# Sheet_2.net
KiCad netlist of a schematic drawn in Altium Designer
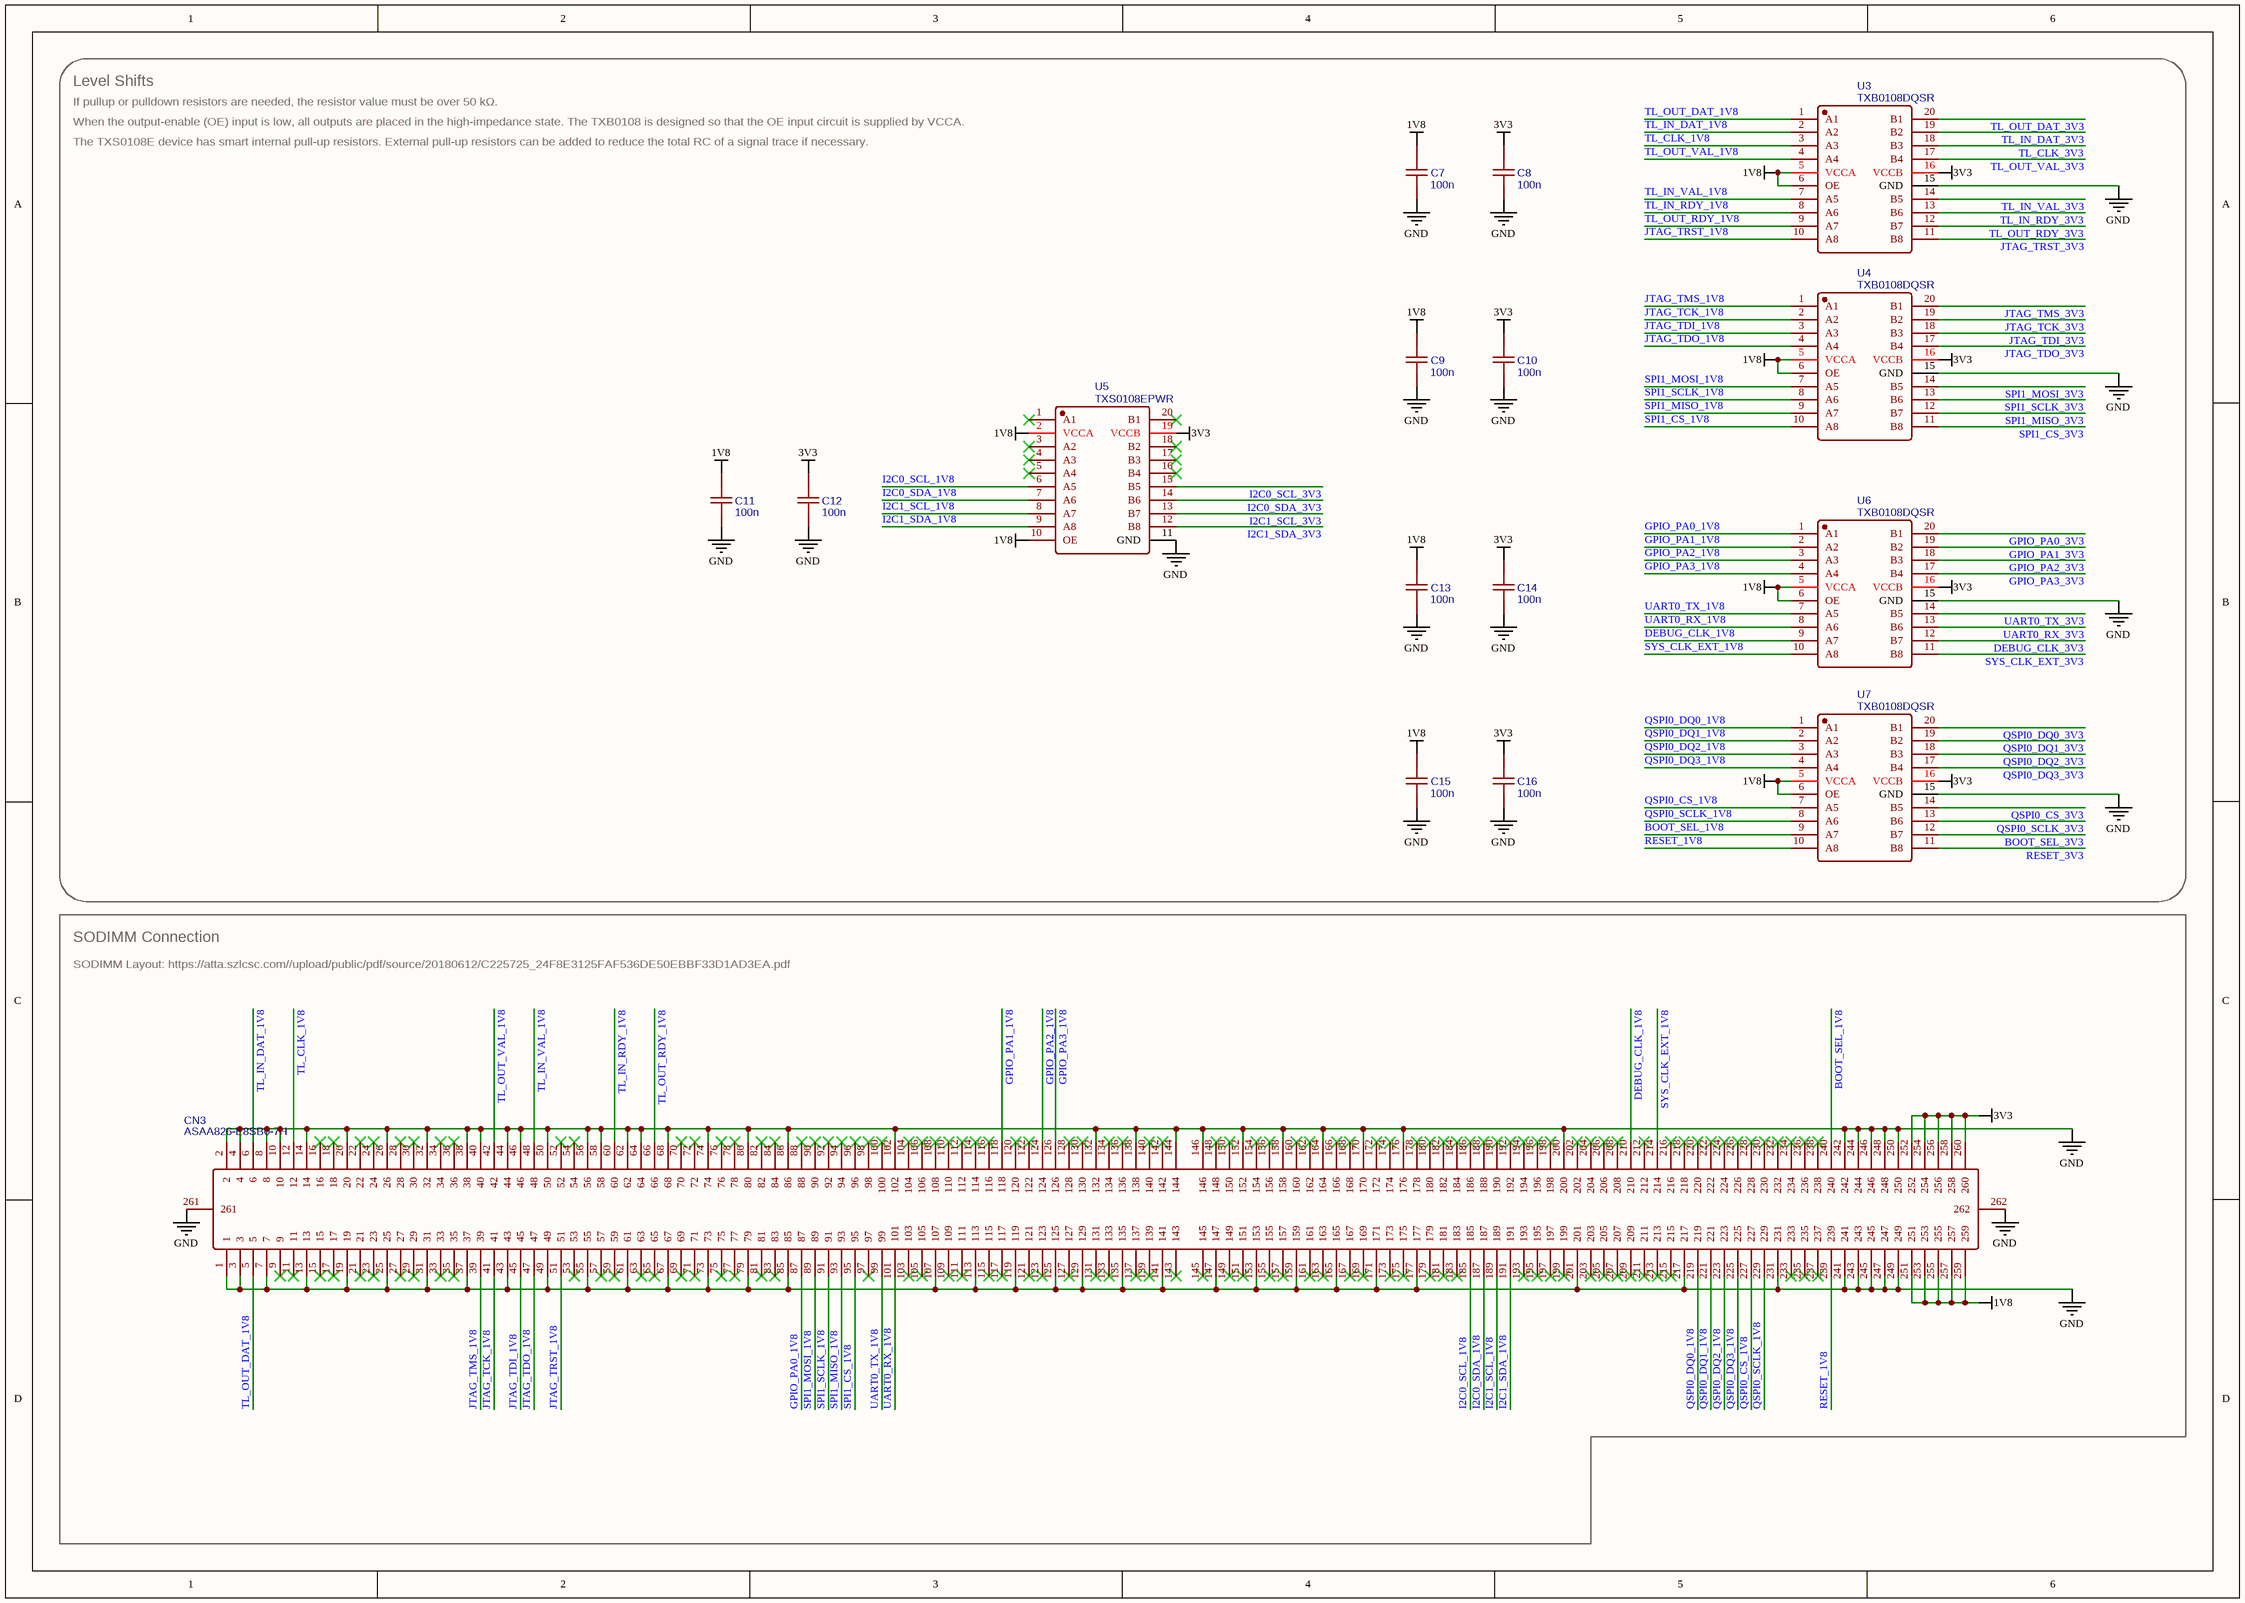
[diagram p0: Sheet_2.schdoc]

(export (version "E")
  (design (tool "Eeschema 10.0.6"))
  (components
    (comp (ref "C7")
      (value "100n")
      (footprint "CAPA-0402")
      (fields
        (field (name "BOM_SUPPLIER PART") "C307331")
        (field (name "BOM_MANUFACTURER PART") "CL05B104KB54PNC")
      )
      (libsource (lib "altium-import") (part "root_1_100n_"))
    )
    (comp (ref "C8")
      (value "100n")
      (footprint "CAPA-0402")
      (fields
        (field (name "BOM_SUPPLIER PART") "C307331")
        (field (name "BOM_MANUFACTURER PART") "CL05B104KB54PNC")
      )
      (libsource (lib "altium-import") (part "root_1_100n_"))
    )
    (comp (ref "C9")
      (value "100n")
      (footprint "CAPA-0402")
      (fields
        (field (name "BOM_SUPPLIER PART") "C307331")
        (field (name "BOM_MANUFACTURER PART") "CL05B104KB54PNC")
      )
      (libsource (lib "altium-import") (part "root_1_100n_"))
    )
    (comp (ref "C10")
      (value "100n")
      (footprint "CAPA-0402")
      (fields
        (field (name "BOM_SUPPLIER PART") "C307331")
        (field (name "BOM_MANUFACTURER PART") "CL05B104KB54PNC")
      )
      (libsource (lib "altium-import") (part "root_1_100n_"))
    )
    (comp (ref "C11")
      (value "100n")
      (footprint "CAPA-0402")
      (fields
        (field (name "BOM_SUPPLIER PART") "C307331")
        (field (name "BOM_MANUFACTURER PART") "CL05B104KB54PNC")
      )
      (libsource (lib "altium-import") (part "root_1_100n_"))
    )
    (comp (ref "C12")
      (value "100n")
      (footprint "CAPA-0402")
      (fields
        (field (name "BOM_SUPPLIER PART") "C307331")
        (field (name "BOM_MANUFACTURER PART") "CL05B104KB54PNC")
      )
      (libsource (lib "altium-import") (part "root_1_100n_"))
    )
    (comp (ref "C13")
      (value "100n")
      (footprint "CAPA-0402")
      (fields
        (field (name "BOM_SUPPLIER PART") "C307331")
        (field (name "BOM_MANUFACTURER PART") "CL05B104KB54PNC")
      )
      (libsource (lib "altium-import") (part "root_1_100n_"))
    )
    (comp (ref "C14")
      (value "100n")
      (footprint "CAPA-0402")
      (fields
        (field (name "BOM_SUPPLIER PART") "C307331")
        (field (name "BOM_MANUFACTURER PART") "CL05B104KB54PNC")
      )
      (libsource (lib "altium-import") (part "root_1_100n_"))
    )
    (comp (ref "C15")
      (value "100n")
      (footprint "CAPA-0402")
      (fields
        (field (name "BOM_SUPPLIER PART") "C307331")
        (field (name "BOM_MANUFACTURER PART") "CL05B104KB54PNC")
      )
      (libsource (lib "altium-import") (part "root_1_100n_"))
    )
    (comp (ref "C16")
      (value "100n")
      (footprint "CAPA-0402")
      (fields
        (field (name "BOM_SUPPLIER PART") "C307331")
        (field (name "BOM_MANUFACTURER PART") "CL05B104KB54PNC")
      )
      (libsource (lib "altium-import") (part "root_1_100n_"))
    )
    (comp (ref "CN3")
      (value "ASAA826-E8SB0-7H")
      (footprint "CONN-SMD_ASAA826-E8SB0-7H")
      (fields (field (name "BOM_SUPPLIER PART") "C2761395"))
      (libsource (lib "altium-import") (part "root_0_ASAA826-E8SB0-7H_"))
    )
    (comp (ref "U3")
      (value "TXB0108DQSR")
      (footprint "SON-20_L4.0-W2.0-P0.40-BL")
      (fields (field (name "BOM_SUPPLIER PART") "C427057"))
      (libsource (lib "altium-import") (part "root_0_TXB0108DQSR_"))
    )
    (comp (ref "U4")
      (value "TXB0108DQSR")
      (footprint "SON-20_L4.0-W2.0-P0.40-BL")
      (fields (field (name "BOM_SUPPLIER PART") "C427057"))
      (libsource (lib "altium-import") (part "root_0_TXB0108DQSR_"))
    )
    (comp (ref "U5")
      (value "TXS0108EPWR")
      (footprint "TSSOP-20_L6.5-W4.4-P0.65-LS6.4-BL")
      (fields (field (name "BOM_SUPPLIER PART") "C17206"))
      (libsource (lib "altium-import") (part "root_0_TXS0108EPWR_"))
    )
    (comp (ref "U6")
      (value "TXB0108DQSR")
      (footprint "SON-20_L4.0-W2.0-P0.40-BL")
      (fields (field (name "BOM_SUPPLIER PART") "C427057"))
      (libsource (lib "altium-import") (part "root_0_TXB0108DQSR_"))
    )
    (comp (ref "U7")
      (value "TXB0108DQSR")
      (footprint "SON-20_L4.0-W2.0-P0.40-BL")
      (fields (field (name "BOM_SUPPLIER PART") "C427057"))
      (libsource (lib "altium-import") (part "root_0_TXB0108DQSR_"))
    )
  )
  (nets
    (net (code "1") (name "/BOOT_SEL_1V8") (class "Default")
      (node (ref "CN3") (pin "240") (pinfunction "240_240") (pintype "passive"))
      (node (ref "U7") (pin "9") (pinfunction "A7_9") (pintype "passive"))
    )
    (net (code "2") (name "/BOOT_SEL_3V3") (class "Default")
      (node (ref "U7") (pin "12") (pinfunction "B7_12") (pintype "passive"))
    )
    (net (code "3") (name "/DEBUG_CLK_1V8") (class "Default")
      (node (ref "CN3") (pin "210") (pinfunction "210_210") (pintype "passive"))
      (node (ref "U6") (pin "9") (pinfunction "A7_9") (pintype "passive"))
    )
    (net (code "4") (name "/DEBUG_CLK_3V3") (class "Default")
      (node (ref "U6") (pin "12") (pinfunction "B7_12") (pintype "passive"))
    )
    (net (code "5") (name "/GPIO_PA0_1V8") (class "Default")
      (node (ref "CN3") (pin "87") (pinfunction "87_87") (pintype "passive"))
      (node (ref "U6") (pin "1") (pinfunction "A1_1") (pintype "passive"))
    )
    (net (code "6") (name "/GPIO_PA0_3V3") (class "Default")
      (node (ref "U6") (pin "20") (pinfunction "B1_20") (pintype "passive"))
    )
    (net (code "7") (name "/GPIO_PA1_1V8") (class "Default")
      (node (ref "CN3") (pin "118") (pinfunction "118_118") (pintype "passive"))
      (node (ref "U6") (pin "2") (pinfunction "A2_2") (pintype "passive"))
    )
    (net (code "8") (name "/GPIO_PA1_3V3") (class "Default")
      (node (ref "U6") (pin "19") (pinfunction "B2_19") (pintype "passive"))
    )
    (net (code "9") (name "/GPIO_PA2_1V8") (class "Default")
      (node (ref "CN3") (pin "124") (pinfunction "124_124") (pintype "passive"))
      (node (ref "U6") (pin "3") (pinfunction "A3_3") (pintype "passive"))
    )
    (net (code "10") (name "/GPIO_PA2_3V3") (class "Default")
      (node (ref "U6") (pin "18") (pinfunction "B3_18") (pintype "passive"))
    )
    (net (code "11") (name "/GPIO_PA3_1V8") (class "Default")
      (node (ref "CN3") (pin "126") (pinfunction "126_126") (pintype "passive"))
      (node (ref "U6") (pin "4") (pinfunction "A4_4") (pintype "passive"))
    )
    (net (code "12") (name "/GPIO_PA3_3V3") (class "Default")
      (node (ref "U6") (pin "17") (pinfunction "B4_17") (pintype "passive"))
    )
    (net (code "13") (name "/I2C0_SCL_1V8") (class "Default")
      (node (ref "CN3") (pin "185") (pinfunction "185_185") (pintype "passive"))
      (node (ref "U5") (pin "6") (pinfunction "A5_6") (pintype "passive"))
    )
    (net (code "14") (name "/I2C0_SCL_3V3") (class "Default")
      (node (ref "U5") (pin "15") (pinfunction "B5_15") (pintype "passive"))
    )
    (net (code "15") (name "/I2C0_SDA_1V8") (class "Default")
      (node (ref "CN3") (pin "187") (pinfunction "187_187") (pintype "passive"))
      (node (ref "U5") (pin "7") (pinfunction "A6_7") (pintype "passive"))
    )
    (net (code "16") (name "/I2C0_SDA_3V3") (class "Default")
      (node (ref "U5") (pin "14") (pinfunction "B6_14") (pintype "passive"))
    )
    (net (code "17") (name "/I2C1_SCL_1V8") (class "Default")
      (node (ref "CN3") (pin "189") (pinfunction "189_189") (pintype "passive"))
      (node (ref "U5") (pin "8") (pinfunction "A7_8") (pintype "passive"))
    )
    (net (code "18") (name "/I2C1_SCL_3V3") (class "Default")
      (node (ref "U5") (pin "13") (pinfunction "B7_13") (pintype "passive"))
    )
    (net (code "19") (name "/I2C1_SDA_1V8") (class "Default")
      (node (ref "CN3") (pin "191") (pinfunction "191_191") (pintype "passive"))
      (node (ref "U5") (pin "9") (pinfunction "A8_9") (pintype "passive"))
    )
    (net (code "20") (name "/I2C1_SDA_3V3") (class "Default")
      (node (ref "U5") (pin "12") (pinfunction "B8_12") (pintype "passive"))
    )
    (net (code "21") (name "/JTAG_TCK_1V8") (class "Default")
      (node (ref "CN3") (pin "41") (pinfunction "41_41") (pintype "passive"))
      (node (ref "U4") (pin "2") (pinfunction "A2_2") (pintype "passive"))
    )
    (net (code "22") (name "/JTAG_TCK_3V3") (class "Default")
      (node (ref "U4") (pin "19") (pinfunction "B2_19") (pintype "passive"))
    )
    (net (code "23") (name "/JTAG_TDI_1V8") (class "Default")
      (node (ref "CN3") (pin "45") (pinfunction "45_45") (pintype "passive"))
      (node (ref "U4") (pin "3") (pinfunction "A3_3") (pintype "passive"))
    )
    (net (code "24") (name "/JTAG_TDI_3V3") (class "Default")
      (node (ref "U4") (pin "18") (pinfunction "B3_18") (pintype "passive"))
    )
    (net (code "25") (name "/JTAG_TDO_1V8") (class "Default")
      (node (ref "CN3") (pin "47") (pinfunction "47_47") (pintype "passive"))
      (node (ref "U4") (pin "4") (pinfunction "A4_4") (pintype "passive"))
    )
    (net (code "26") (name "/JTAG_TDO_3V3") (class "Default")
      (node (ref "U4") (pin "17") (pinfunction "B4_17") (pintype "passive"))
    )
    (net (code "27") (name "/JTAG_TMS_1V8") (class "Default")
      (node (ref "CN3") (pin "39") (pinfunction "39_39") (pintype "passive"))
      (node (ref "U4") (pin "1") (pinfunction "A1_1") (pintype "passive"))
    )
    (net (code "28") (name "/JTAG_TMS_3V3") (class "Default")
      (node (ref "U4") (pin "20") (pinfunction "B1_20") (pintype "passive"))
    )
    (net (code "29") (name "/JTAG_TRST_1V8") (class "Default")
      (node (ref "CN3") (pin "51") (pinfunction "51_51") (pintype "passive"))
      (node (ref "U3") (pin "10") (pinfunction "A8_10") (pintype "passive"))
    )
    (net (code "30") (name "/JTAG_TRST_3V3") (class "Default")
      (node (ref "U3") (pin "11") (pinfunction "B8_11") (pintype "passive"))
    )
    (net (code "31") (name "/QSPI0_CS_1V8") (class "Default")
      (node (ref "CN3") (pin "227") (pinfunction "227_227") (pintype "passive"))
      (node (ref "U7") (pin "7") (pinfunction "A5_7") (pintype "passive"))
    )
    (net (code "32") (name "/QSPI0_CS_3V3") (class "Default")
      (node (ref "U7") (pin "14") (pinfunction "B5_14") (pintype "passive"))
    )
    (net (code "33") (name "/QSPI0_DQ0_1V8") (class "Default")
      (node (ref "CN3") (pin "219") (pinfunction "219_219") (pintype "passive"))
      (node (ref "U7") (pin "1") (pinfunction "A1_1") (pintype "passive"))
    )
    (net (code "34") (name "/QSPI0_DQ0_3V3") (class "Default")
      (node (ref "U7") (pin "20") (pinfunction "B1_20") (pintype "passive"))
    )
    (net (code "35") (name "/QSPI0_DQ1_1V8") (class "Default")
      (node (ref "CN3") (pin "221") (pinfunction "221_221") (pintype "passive"))
      (node (ref "U7") (pin "2") (pinfunction "A2_2") (pintype "passive"))
    )
    (net (code "36") (name "/QSPI0_DQ1_3V3") (class "Default")
      (node (ref "U7") (pin "19") (pinfunction "B2_19") (pintype "passive"))
    )
    (net (code "37") (name "/QSPI0_DQ2_1V8") (class "Default")
      (node (ref "CN3") (pin "223") (pinfunction "223_223") (pintype "passive"))
      (node (ref "U7") (pin "3") (pinfunction "A3_3") (pintype "passive"))
    )
    (net (code "38") (name "/QSPI0_DQ2_3V3") (class "Default")
      (node (ref "U7") (pin "18") (pinfunction "B3_18") (pintype "passive"))
    )
    (net (code "39") (name "/QSPI0_DQ3_1V8") (class "Default")
      (node (ref "CN3") (pin "225") (pinfunction "225_225") (pintype "passive"))
      (node (ref "U7") (pin "4") (pinfunction "A4_4") (pintype "passive"))
    )
    (net (code "40") (name "/QSPI0_DQ3_3V3") (class "Default")
      (node (ref "U7") (pin "17") (pinfunction "B4_17") (pintype "passive"))
    )
    (net (code "41") (name "/QSPI0_SCLK_1V8") (class "Default")
      (node (ref "CN3") (pin "229") (pinfunction "229_229") (pintype "passive"))
      (node (ref "U7") (pin "8") (pinfunction "A6_8") (pintype "passive"))
    )
    (net (code "42") (name "/QSPI0_SCLK_3V3") (class "Default")
      (node (ref "U7") (pin "13") (pinfunction "B6_13") (pintype "passive"))
    )
    (net (code "43") (name "/RESET_1V8") (class "Default")
      (node (ref "CN3") (pin "239") (pinfunction "239_239") (pintype "passive"))
      (node (ref "U7") (pin "10") (pinfunction "A8_10") (pintype "passive"))
    )
    (net (code "44") (name "/RESET_3V3") (class "Default")
      (node (ref "U7") (pin "11") (pinfunction "B8_11") (pintype "passive"))
    )
    (net (code "45") (name "/SPI1_CS_1V8") (class "Default")
      (node (ref "CN3") (pin "95") (pinfunction "95_95") (pintype "passive"))
      (node (ref "U4") (pin "10") (pinfunction "A8_10") (pintype "passive"))
    )
    (net (code "46") (name "/SPI1_CS_3V3") (class "Default")
      (node (ref "U4") (pin "11") (pinfunction "B8_11") (pintype "passive"))
    )
    (net (code "47") (name "/SPI1_MISO_1V8") (class "Default")
      (node (ref "CN3") (pin "93") (pinfunction "93_93") (pintype "passive"))
      (node (ref "U4") (pin "9") (pinfunction "A7_9") (pintype "passive"))
    )
    (net (code "48") (name "/SPI1_MISO_3V3") (class "Default")
      (node (ref "U4") (pin "12") (pinfunction "B7_12") (pintype "passive"))
    )
    (net (code "49") (name "/SPI1_MOSI_1V8") (class "Default")
      (node (ref "CN3") (pin "89") (pinfunction "89_89") (pintype "passive"))
      (node (ref "U4") (pin "7") (pinfunction "A5_7") (pintype "passive"))
    )
    (net (code "50") (name "/SPI1_MOSI_3V3") (class "Default")
      (node (ref "U4") (pin "14") (pinfunction "B5_14") (pintype "passive"))
    )
    (net (code "51") (name "/SPI1_SCLK_1V8") (class "Default")
      (node (ref "CN3") (pin "91") (pinfunction "91_91") (pintype "passive"))
      (node (ref "U4") (pin "8") (pinfunction "A6_8") (pintype "passive"))
    )
    (net (code "52") (name "/SPI1_SCLK_3V3") (class "Default")
      (node (ref "U4") (pin "13") (pinfunction "B6_13") (pintype "passive"))
    )
    (net (code "53") (name "/SYS_CLK_EXT_1V8") (class "Default")
      (node (ref "CN3") (pin "214") (pinfunction "214_214") (pintype "passive"))
      (node (ref "U6") (pin "10") (pinfunction "A8_10") (pintype "passive"))
    )
    (net (code "54") (name "/SYS_CLK_EXT_3V3") (class "Default")
      (node (ref "U6") (pin "11") (pinfunction "B8_11") (pintype "passive"))
    )
    (net (code "55") (name "/TL_CLK_1V8") (class "Default")
      (node (ref "CN3") (pin "12") (pinfunction "12_12") (pintype "passive"))
      (node (ref "U3") (pin "3") (pinfunction "A3_3") (pintype "passive"))
    )
    (net (code "56") (name "/TL_CLK_3V3") (class "Default")
      (node (ref "U3") (pin "18") (pinfunction "B3_18") (pintype "passive"))
    )
    (net (code "57") (name "/TL_IN_DAT_1V8") (class "Default")
      (node (ref "CN3") (pin "6") (pinfunction "6_6") (pintype "passive"))
      (node (ref "U3") (pin "2") (pinfunction "A2_2") (pintype "passive"))
    )
    (net (code "58") (name "/TL_IN_DAT_3V3") (class "Default")
      (node (ref "U3") (pin "19") (pinfunction "B2_19") (pintype "passive"))
    )
    (net (code "59") (name "/TL_IN_RDY_1V8") (class "Default")
      (node (ref "CN3") (pin "60") (pinfunction "60_60") (pintype "passive"))
      (node (ref "U3") (pin "8") (pinfunction "A6_8") (pintype "passive"))
    )
    (net (code "60") (name "/TL_IN_RDY_3V3") (class "Default")
      (node (ref "U3") (pin "13") (pinfunction "B6_13") (pintype "passive"))
    )
    (net (code "61") (name "/TL_IN_VAL_1V8") (class "Default")
      (node (ref "CN3") (pin "48") (pinfunction "48_48") (pintype "passive"))
      (node (ref "U3") (pin "7") (pinfunction "A5_7") (pintype "passive"))
    )
    (net (code "62") (name "/TL_IN_VAL_3V3") (class "Default")
      (node (ref "U3") (pin "14") (pinfunction "B5_14") (pintype "passive"))
    )
    (net (code "63") (name "/TL_OUT_DAT_1V8") (class "Default")
      (node (ref "CN3") (pin "5") (pinfunction "5_5") (pintype "passive"))
      (node (ref "U3") (pin "1") (pinfunction "A1_1") (pintype "passive"))
    )
    (net (code "64") (name "/TL_OUT_DAT_3V3") (class "Default")
      (node (ref "U3") (pin "20") (pinfunction "B1_20") (pintype "passive"))
    )
    (net (code "65") (name "/TL_OUT_RDY_1V8") (class "Default")
      (node (ref "CN3") (pin "66") (pinfunction "66_66") (pintype "passive"))
      (node (ref "U3") (pin "9") (pinfunction "A7_9") (pintype "passive"))
    )
    (net (code "66") (name "/TL_OUT_RDY_3V3") (class "Default")
      (node (ref "U3") (pin "12") (pinfunction "B7_12") (pintype "passive"))
    )
    (net (code "67") (name "/TL_OUT_VAL_1V8") (class "Default")
      (node (ref "CN3") (pin "42") (pinfunction "42_42") (pintype "passive"))
      (node (ref "U3") (pin "4") (pinfunction "A4_4") (pintype "passive"))
    )
    (net (code "68") (name "/TL_OUT_VAL_3V3") (class "Default")
      (node (ref "U3") (pin "17") (pinfunction "B4_17") (pintype "passive"))
    )
    (net (code "69") (name "/UART0_RX_1V8") (class "Default")
      (node (ref "CN3") (pin "101") (pinfunction "101_101") (pintype "passive"))
      (node (ref "U6") (pin "8") (pinfunction "A6_8") (pintype "passive"))
    )
    (net (code "70") (name "/UART0_RX_3V3") (class "Default")
      (node (ref "U6") (pin "13") (pinfunction "B6_13") (pintype "passive"))
    )
    (net (code "71") (name "/UART0_TX_1V8") (class "Default")
      (node (ref "CN3") (pin "99") (pinfunction "99_99") (pintype "passive"))
      (node (ref "U6") (pin "7") (pinfunction "A5_7") (pintype "passive"))
    )
    (net (code "72") (name "/UART0_TX_3V3") (class "Default")
      (node (ref "U6") (pin "14") (pinfunction "B5_14") (pintype "passive"))
    )
    (net (code "73") (name "1V8") (class "Default")
      (node (ref "C11") (pin "2") (pinfunction "2_2") (pintype "passive"))
      (node (ref "C13") (pin "2") (pinfunction "2_2") (pintype "passive"))
      (node (ref "C15") (pin "2") (pinfunction "2_2") (pintype "passive"))
      (node (ref "C7") (pin "2") (pinfunction "2_2") (pintype "passive"))
      (node (ref "C9") (pin "2") (pinfunction "2_2") (pintype "passive"))
      (node (ref "CN3") (pin "251") (pinfunction "251_251") (pintype "passive"))
      (node (ref "CN3") (pin "253") (pinfunction "253_253") (pintype "passive"))
      (node (ref "CN3") (pin "255") (pinfunction "255_255") (pintype "passive"))
      (node (ref "CN3") (pin "257") (pinfunction "257_257") (pintype "passive"))
      (node (ref "CN3") (pin "259") (pinfunction "259_259") (pintype "passive"))
      (node (ref "U3") (pin "5") (pinfunction "VCCA_5") (pintype "passive"))
      (node (ref "U3") (pin "6") (pinfunction "OE_6") (pintype "passive"))
      (node (ref "U4") (pin "5") (pinfunction "VCCA_5") (pintype "passive"))
      (node (ref "U4") (pin "6") (pinfunction "OE_6") (pintype "passive"))
      (node (ref "U5") (pin "10") (pinfunction "OE_10") (pintype "passive"))
      (node (ref "U5") (pin "2") (pinfunction "VCCA_2") (pintype "passive"))
      (node (ref "U6") (pin "5") (pinfunction "VCCA_5") (pintype "passive"))
      (node (ref "U6") (pin "6") (pinfunction "OE_6") (pintype "passive"))
      (node (ref "U7") (pin "5") (pinfunction "VCCA_5") (pintype "passive"))
      (node (ref "U7") (pin "6") (pinfunction "OE_6") (pintype "passive"))
    )
    (net (code "74") (name "3V3") (class "Default")
      (node (ref "C10") (pin "2") (pinfunction "2_2") (pintype "passive"))
      (node (ref "C12") (pin "2") (pinfunction "2_2") (pintype "passive"))
      (node (ref "C14") (pin "2") (pinfunction "2_2") (pintype "passive"))
      (node (ref "C16") (pin "2") (pinfunction "2_2") (pintype "passive"))
      (node (ref "C8") (pin "2") (pinfunction "2_2") (pintype "passive"))
      (node (ref "CN3") (pin "252") (pinfunction "252_252") (pintype "passive"))
      (node (ref "CN3") (pin "254") (pinfunction "254_254") (pintype "passive"))
      (node (ref "CN3") (pin "256") (pinfunction "256_256") (pintype "passive"))
      (node (ref "CN3") (pin "258") (pinfunction "258_258") (pintype "passive"))
      (node (ref "CN3") (pin "260") (pinfunction "260_260") (pintype "passive"))
      (node (ref "U3") (pin "16") (pinfunction "VCCB_16") (pintype "passive"))
      (node (ref "U4") (pin "16") (pinfunction "VCCB_16") (pintype "passive"))
      (node (ref "U5") (pin "19") (pinfunction "VCCB_19") (pintype "passive"))
      (node (ref "U6") (pin "16") (pinfunction "VCCB_16") (pintype "passive"))
      (node (ref "U7") (pin "16") (pinfunction "VCCB_16") (pintype "passive"))
    )
    (net (code "75") (name "GND") (class "Default")
      (node (ref "C10") (pin "1") (pinfunction "1_1") (pintype "passive"))
      (node (ref "C11") (pin "1") (pinfunction "1_1") (pintype "passive"))
      (node (ref "C12") (pin "1") (pinfunction "1_1") (pintype "passive"))
      (node (ref "C13") (pin "1") (pinfunction "1_1") (pintype "passive"))
      (node (ref "C14") (pin "1") (pinfunction "1_1") (pintype "passive"))
      (node (ref "C15") (pin "1") (pinfunction "1_1") (pintype "passive"))
      (node (ref "C16") (pin "1") (pinfunction "1_1") (pintype "passive"))
      (node (ref "C7") (pin "1") (pinfunction "1_1") (pintype "passive"))
      (node (ref "C8") (pin "1") (pinfunction "1_1") (pintype "passive"))
      (node (ref "C9") (pin "1") (pinfunction "1_1") (pintype "passive"))
      (node (ref "CN3") (pin "1") (pinfunction "1_1") (pintype "passive"))
      (node (ref "CN3") (pin "10") (pinfunction "10_10") (pintype "passive"))
      (node (ref "CN3") (pin "102") (pinfunction "102_102") (pintype "passive"))
      (node (ref "CN3") (pin "107") (pinfunction "107_107") (pintype "passive"))
      (node (ref "CN3") (pin "113") (pinfunction "113_113") (pintype "passive"))
      (node (ref "CN3") (pin "119") (pinfunction "119_119") (pintype "passive"))
      (node (ref "CN3") (pin "125") (pinfunction "125_125") (pintype "passive"))
      (node (ref "CN3") (pin "129") (pinfunction "129_129") (pintype "passive"))
      (node (ref "CN3") (pin "13") (pinfunction "13_13") (pintype "passive"))
      (node (ref "CN3") (pin "132") (pinfunction "132_132") (pintype "passive"))
      (node (ref "CN3") (pin "135") (pinfunction "135_135") (pintype "passive"))
      (node (ref "CN3") (pin "138") (pinfunction "138_138") (pintype "passive"))
      (node (ref "CN3") (pin "14") (pinfunction "14_14") (pintype "passive"))
      (node (ref "CN3") (pin "141") (pinfunction "141_141") (pintype "passive"))
      (node (ref "CN3") (pin "144") (pinfunction "144_144") (pintype "passive"))
      (node (ref "CN3") (pin "146") (pinfunction "146_146") (pintype "passive"))
      (node (ref "CN3") (pin "147") (pinfunction "147_147") (pintype "passive"))
      (node (ref "CN3") (pin "152") (pinfunction "152_152") (pintype "passive"))
      (node (ref "CN3") (pin "153") (pinfunction "153_153") (pintype "passive"))
      (node (ref "CN3") (pin "158") (pinfunction "158_158") (pintype "passive"))
      (node (ref "CN3") (pin "159") (pinfunction "159_159") (pintype "passive"))
      (node (ref "CN3") (pin "164") (pinfunction "164_164") (pintype "passive"))
      (node (ref "CN3") (pin "165") (pinfunction "165_165") (pintype "passive"))
      (node (ref "CN3") (pin "170") (pinfunction "170_170") (pintype "passive"))
      (node (ref "CN3") (pin "171") (pinfunction "171_171") (pintype "passive"))
      (node (ref "CN3") (pin "176") (pinfunction "176_176") (pintype "passive"))
      (node (ref "CN3") (pin "177") (pinfunction "177_177") (pintype "passive"))
      (node (ref "CN3") (pin "19") (pinfunction "19_19") (pintype "passive"))
      (node (ref "CN3") (pin "2") (pinfunction "2_2") (pintype "passive"))
      (node (ref "CN3") (pin "20") (pinfunction "20_20") (pintype "passive"))
      (node (ref "CN3") (pin "200") (pinfunction "200_200") (pintype "passive"))
      (node (ref "CN3") (pin "201") (pinfunction "201_201") (pintype "passive"))
      (node (ref "CN3") (pin "217") (pinfunction "217_217") (pintype "passive"))
      (node (ref "CN3") (pin "231") (pinfunction "231_231") (pintype "passive"))
      (node (ref "CN3") (pin "241") (pinfunction "241_241") (pintype "passive"))
      (node (ref "CN3") (pin "242") (pinfunction "242_242") (pintype "passive"))
      (node (ref "CN3") (pin "243") (pinfunction "243_243") (pintype "passive"))
      (node (ref "CN3") (pin "244") (pinfunction "244_244") (pintype "passive"))
      (node (ref "CN3") (pin "245") (pinfunction "245_245") (pintype "passive"))
      (node (ref "CN3") (pin "246") (pinfunction "246_246") (pintype "passive"))
      (node (ref "CN3") (pin "247") (pinfunction "247_247") (pintype "passive"))
      (node (ref "CN3") (pin "248") (pinfunction "248_248") (pintype "passive"))
      (node (ref "CN3") (pin "249") (pinfunction "249_249") (pintype "passive"))
      (node (ref "CN3") (pin "25") (pinfunction "25_25") (pintype "passive"))
      (node (ref "CN3") (pin "250") (pinfunction "250_250") (pintype "passive"))
      (node (ref "CN3") (pin "26") (pinfunction "26_26") (pintype "passive"))
      (node (ref "CN3") (pin "261") (pinfunction "261_261") (pintype "passive"))
      (node (ref "CN3") (pin "262") (pinfunction "262_262") (pintype "passive"))
      (node (ref "CN3") (pin "3") (pinfunction "3_3") (pintype "passive"))
      (node (ref "CN3") (pin "31") (pinfunction "31_31") (pintype "passive"))
      (node (ref "CN3") (pin "32") (pinfunction "32_32") (pintype "passive"))
      (node (ref "CN3") (pin "37") (pinfunction "37_37") (pintype "passive"))
      (node (ref "CN3") (pin "38") (pinfunction "38_38") (pintype "passive"))
      (node (ref "CN3") (pin "4") (pinfunction "4_4") (pintype "passive"))
      (node (ref "CN3") (pin "40") (pinfunction "40_40") (pintype "passive"))
      (node (ref "CN3") (pin "43") (pinfunction "43_43") (pintype "passive"))
      (node (ref "CN3") (pin "44") (pinfunction "44_44") (pintype "passive"))
      (node (ref "CN3") (pin "46") (pinfunction "46_46") (pintype "passive"))
      (node (ref "CN3") (pin "49") (pinfunction "49_49") (pintype "passive"))
      (node (ref "CN3") (pin "50") (pinfunction "50_50") (pintype "passive"))
      (node (ref "CN3") (pin "55") (pinfunction "55_55") (pintype "passive"))
      (node (ref "CN3") (pin "56") (pinfunction "56_56") (pintype "passive"))
      (node (ref "CN3") (pin "58") (pinfunction "58_58") (pintype "passive"))
      (node (ref "CN3") (pin "61") (pinfunction "61_61") (pintype "passive"))
      (node (ref "CN3") (pin "62") (pinfunction "62_62") (pintype "passive"))
      (node (ref "CN3") (pin "64") (pinfunction "64_64") (pintype "passive"))
      (node (ref "CN3") (pin "67") (pinfunction "67_67") (pintype "passive"))
      (node (ref "CN3") (pin "68") (pinfunction "68_68") (pintype "passive"))
      (node (ref "CN3") (pin "7") (pinfunction "7_7") (pintype "passive"))
      (node (ref "CN3") (pin "73") (pinfunction "73_73") (pintype "passive"))
      (node (ref "CN3") (pin "74") (pinfunction "74_74") (pintype "passive"))
      (node (ref "CN3") (pin "79") (pinfunction "79_79") (pintype "passive"))
      (node (ref "CN3") (pin "8") (pinfunction "8_8") (pintype "passive"))
      (node (ref "CN3") (pin "80") (pinfunction "80_80") (pintype "passive"))
      (node (ref "CN3") (pin "85") (pinfunction "85_85") (pintype "passive"))
      (node (ref "CN3") (pin "86") (pinfunction "86_86") (pintype "passive"))
      (node (ref "U3") (pin "15") (pinfunction "GND_15") (pintype "passive"))
      (node (ref "U4") (pin "15") (pinfunction "GND_15") (pintype "passive"))
      (node (ref "U5") (pin "11") (pinfunction "GND_11") (pintype "passive"))
      (node (ref "U6") (pin "15") (pinfunction "GND_15") (pintype "passive"))
      (node (ref "U7") (pin "15") (pinfunction "GND_15") (pintype "passive"))
    )
    (net (code "76") (name "unconnected-(CN3-Pad9)") (class "Default")
      (node (ref "CN3") (pin "9") (pinfunction "9_9") (pintype "passive+no_connect"))
    )
    (net (code "77") (name "unconnected-(CN3-Pad11)") (class "Default")
      (node (ref "CN3") (pin "11") (pinfunction "11_11") (pintype "passive+no_connect"))
    )
    (net (code "78") (name "unconnected-(CN3-Pad15)") (class "Default")
      (node (ref "CN3") (pin "15") (pinfunction "15_15") (pintype "passive+no_connect"))
    )
    (net (code "79") (name "unconnected-(CN3-Pad16)") (class "Default")
      (node (ref "CN3") (pin "16") (pinfunction "16_16") (pintype "passive+no_connect"))
    )
    (net (code "80") (name "unconnected-(CN3-Pad17)") (class "Default")
      (node (ref "CN3") (pin "17") (pinfunction "17_17") (pintype "passive+no_connect"))
    )
    (net (code "81") (name "unconnected-(CN3-Pad18)") (class "Default")
      (node (ref "CN3") (pin "18") (pinfunction "18_18") (pintype "passive+no_connect"))
    )
    (net (code "82") (name "unconnected-(CN3-Pad21)") (class "Default")
      (node (ref "CN3") (pin "21") (pinfunction "21_21") (pintype "passive+no_connect"))
    )
    (net (code "83") (name "unconnected-(CN3-Pad22)") (class "Default")
      (node (ref "CN3") (pin "22") (pinfunction "22_22") (pintype "passive+no_connect"))
    )
    (net (code "84") (name "unconnected-(CN3-Pad23)") (class "Default")
      (node (ref "CN3") (pin "23") (pinfunction "23_23") (pintype "passive+no_connect"))
    )
    (net (code "85") (name "unconnected-(CN3-Pad24)") (class "Default")
      (node (ref "CN3") (pin "24") (pinfunction "24_24") (pintype "passive+no_connect"))
    )
    (net (code "86") (name "unconnected-(CN3-Pad27)") (class "Default")
      (node (ref "CN3") (pin "27") (pinfunction "27_27") (pintype "passive+no_connect"))
    )
    (net (code "87") (name "unconnected-(CN3-Pad28)") (class "Default")
      (node (ref "CN3") (pin "28") (pinfunction "28_28") (pintype "passive+no_connect"))
    )
    (net (code "88") (name "unconnected-(CN3-Pad29)") (class "Default")
      (node (ref "CN3") (pin "29") (pinfunction "29_29") (pintype "passive+no_connect"))
    )
    (net (code "89") (name "unconnected-(CN3-Pad30)") (class "Default")
      (node (ref "CN3") (pin "30") (pinfunction "30_30") (pintype "passive+no_connect"))
    )
    (net (code "90") (name "unconnected-(CN3-Pad33)") (class "Default")
      (node (ref "CN3") (pin "33") (pinfunction "33_33") (pintype "passive+no_connect"))
    )
    (net (code "91") (name "unconnected-(CN3-Pad34)") (class "Default")
      (node (ref "CN3") (pin "34") (pinfunction "34_34") (pintype "passive+no_connect"))
    )
    (net (code "92") (name "unconnected-(CN3-Pad35)") (class "Default")
      (node (ref "CN3") (pin "35") (pinfunction "35_35") (pintype "passive+no_connect"))
    )
    (net (code "93") (name "unconnected-(CN3-Pad36)") (class "Default")
      (node (ref "CN3") (pin "36") (pinfunction "36_36") (pintype "passive+no_connect"))
    )
    (net (code "94") (name "unconnected-(CN3-Pad52)") (class "Default")
      (node (ref "CN3") (pin "52") (pinfunction "52_52") (pintype "passive+no_connect"))
    )
    (net (code "95") (name "unconnected-(CN3-Pad53)") (class "Default")
      (node (ref "CN3") (pin "53") (pinfunction "53_53") (pintype "passive+no_connect"))
    )
    (net (code "96") (name "unconnected-(CN3-Pad54)") (class "Default")
      (node (ref "CN3") (pin "54") (pinfunction "54_54") (pintype "passive+no_connect"))
    )
    (net (code "97") (name "unconnected-(CN3-Pad57)") (class "Default")
      (node (ref "CN3") (pin "57") (pinfunction "57_57") (pintype "passive+no_connect"))
    )
    (net (code "98") (name "unconnected-(CN3-Pad59)") (class "Default")
      (node (ref "CN3") (pin "59") (pinfunction "59_59") (pintype "passive+no_connect"))
    )
    (net (code "99") (name "unconnected-(CN3-Pad63)") (class "Default")
      (node (ref "CN3") (pin "63") (pinfunction "63_63") (pintype "passive+no_connect"))
    )
    (net (code "100") (name "unconnected-(CN3-Pad65)") (class "Default")
      (node (ref "CN3") (pin "65") (pinfunction "65_65") (pintype "passive+no_connect"))
    )
    (net (code "101") (name "unconnected-(CN3-Pad69)") (class "Default")
      (node (ref "CN3") (pin "69") (pinfunction "69_69") (pintype "passive+no_connect"))
    )
    (net (code "102") (name "unconnected-(CN3-Pad70)") (class "Default")
      (node (ref "CN3") (pin "70") (pinfunction "70_70") (pintype "passive+no_connect"))
    )
    (net (code "103") (name "unconnected-(CN3-Pad71)") (class "Default")
      (node (ref "CN3") (pin "71") (pinfunction "71_71") (pintype "passive+no_connect"))
    )
    (net (code "104") (name "unconnected-(CN3-Pad72)") (class "Default")
      (node (ref "CN3") (pin "72") (pinfunction "72_72") (pintype "passive+no_connect"))
    )
    (net (code "105") (name "unconnected-(CN3-Pad75)") (class "Default")
      (node (ref "CN3") (pin "75") (pinfunction "75_75") (pintype "passive+no_connect"))
    )
    (net (code "106") (name "unconnected-(CN3-Pad76)") (class "Default")
      (node (ref "CN3") (pin "76") (pinfunction "76_76") (pintype "passive+no_connect"))
    )
    (net (code "107") (name "unconnected-(CN3-Pad77)") (class "Default")
      (node (ref "CN3") (pin "77") (pinfunction "77_77") (pintype "passive+no_connect"))
    )
    (net (code "108") (name "unconnected-(CN3-Pad78)") (class "Default")
      (node (ref "CN3") (pin "78") (pinfunction "78_78") (pintype "passive+no_connect"))
    )
    (net (code "109") (name "unconnected-(CN3-Pad81)") (class "Default")
      (node (ref "CN3") (pin "81") (pinfunction "81_81") (pintype "passive+no_connect"))
    )
    (net (code "110") (name "unconnected-(CN3-Pad82)") (class "Default")
      (node (ref "CN3") (pin "82") (pinfunction "82_82") (pintype "passive+no_connect"))
    )
    (net (code "111") (name "unconnected-(CN3-Pad83)") (class "Default")
      (node (ref "CN3") (pin "83") (pinfunction "83_83") (pintype "passive+no_connect"))
    )
    (net (code "112") (name "unconnected-(CN3-Pad84)") (class "Default")
      (node (ref "CN3") (pin "84") (pinfunction "84_84") (pintype "passive+no_connect"))
    )
    (net (code "113") (name "unconnected-(CN3-Pad88)") (class "Default")
      (node (ref "CN3") (pin "88") (pinfunction "88_88") (pintype "passive+no_connect"))
    )
    (net (code "114") (name "unconnected-(CN3-Pad90)") (class "Default")
      (node (ref "CN3") (pin "90") (pinfunction "90_90") (pintype "passive+no_connect"))
    )
    (net (code "115") (name "unconnected-(CN3-Pad92)") (class "Default")
      (node (ref "CN3") (pin "92") (pinfunction "92_92") (pintype "passive+no_connect"))
    )
    (net (code "116") (name "unconnected-(CN3-Pad94)") (class "Default")
      (node (ref "CN3") (pin "94") (pinfunction "94_94") (pintype "passive+no_connect"))
    )
    (net (code "117") (name "unconnected-(CN3-Pad96)") (class "Default")
      (node (ref "CN3") (pin "96") (pinfunction "96_96") (pintype "passive+no_connect"))
    )
    (net (code "118") (name "unconnected-(CN3-Pad97)") (class "Default")
      (node (ref "CN3") (pin "97") (pinfunction "97_97") (pintype "passive+no_connect"))
    )
    (net (code "119") (name "unconnected-(CN3-Pad98)") (class "Default")
      (node (ref "CN3") (pin "98") (pinfunction "98_98") (pintype "passive+no_connect"))
    )
    (net (code "120") (name "unconnected-(CN3-Pad100)") (class "Default")
      (node (ref "CN3") (pin "100") (pinfunction "100_100") (pintype "passive+no_connect"))
    )
    (net (code "121") (name "unconnected-(CN3-Pad103)") (class "Default")
      (node (ref "CN3") (pin "103") (pinfunction "103_103") (pintype "passive+no_connect"))
    )
    (net (code "122") (name "unconnected-(CN3-Pad104)") (class "Default")
      (node (ref "CN3") (pin "104") (pinfunction "104_104") (pintype "passive+no_connect"))
    )
    (net (code "123") (name "unconnected-(CN3-Pad105)") (class "Default")
      (node (ref "CN3") (pin "105") (pinfunction "105_105") (pintype "passive+no_connect"))
    )
    (net (code "124") (name "unconnected-(CN3-Pad106)") (class "Default")
      (node (ref "CN3") (pin "106") (pinfunction "106_106") (pintype "passive+no_connect"))
    )
    (net (code "125") (name "unconnected-(CN3-Pad108)") (class "Default")
      (node (ref "CN3") (pin "108") (pinfunction "108_108") (pintype "passive+no_connect"))
    )
    (net (code "126") (name "unconnected-(CN3-Pad109)") (class "Default")
      (node (ref "CN3") (pin "109") (pinfunction "109_109") (pintype "passive+no_connect"))
    )
    (net (code "127") (name "unconnected-(CN3-Pad110)") (class "Default")
      (node (ref "CN3") (pin "110") (pinfunction "110_110") (pintype "passive+no_connect"))
    )
    (net (code "128") (name "unconnected-(CN3-Pad111)") (class "Default")
      (node (ref "CN3") (pin "111") (pinfunction "111_111") (pintype "passive+no_connect"))
    )
    (net (code "129") (name "unconnected-(CN3-Pad112)") (class "Default")
      (node (ref "CN3") (pin "112") (pinfunction "112_112") (pintype "passive+no_connect"))
    )
    (net (code "130") (name "unconnected-(CN3-Pad114)") (class "Default")
      (node (ref "CN3") (pin "114") (pinfunction "114_114") (pintype "passive+no_connect"))
    )
    (net (code "131") (name "unconnected-(CN3-Pad115)") (class "Default")
      (node (ref "CN3") (pin "115") (pinfunction "115_115") (pintype "passive+no_connect"))
    )
    (net (code "132") (name "unconnected-(CN3-Pad116)") (class "Default")
      (node (ref "CN3") (pin "116") (pinfunction "116_116") (pintype "passive+no_connect"))
    )
    (net (code "133") (name "unconnected-(CN3-Pad117)") (class "Default")
      (node (ref "CN3") (pin "117") (pinfunction "117_117") (pintype "passive+no_connect"))
    )
    (net (code "134") (name "unconnected-(CN3-Pad120)") (class "Default")
      (node (ref "CN3") (pin "120") (pinfunction "120_120") (pintype "passive+no_connect"))
    )
    (net (code "135") (name "unconnected-(CN3-Pad121)") (class "Default")
      (node (ref "CN3") (pin "121") (pinfunction "121_121") (pintype "passive+no_connect"))
    )
    (net (code "136") (name "unconnected-(CN3-Pad122)") (class "Default")
      (node (ref "CN3") (pin "122") (pinfunction "122_122") (pintype "passive+no_connect"))
    )
    (net (code "137") (name "unconnected-(CN3-Pad123)") (class "Default")
      (node (ref "CN3") (pin "123") (pinfunction "123_123") (pintype "passive+no_connect"))
    )
    (net (code "138") (name "unconnected-(CN3-Pad127)") (class "Default")
      (node (ref "CN3") (pin "127") (pinfunction "127_127") (pintype "passive+no_connect"))
    )
    (net (code "139") (name "unconnected-(CN3-Pad128)") (class "Default")
      (node (ref "CN3") (pin "128") (pinfunction "128_128") (pintype "passive+no_connect"))
    )
    (net (code "140") (name "unconnected-(CN3-Pad130)") (class "Default")
      (node (ref "CN3") (pin "130") (pinfunction "130_130") (pintype "passive+no_connect"))
    )
    (net (code "141") (name "unconnected-(CN3-Pad131)") (class "Default")
      (node (ref "CN3") (pin "131") (pinfunction "131_131") (pintype "passive+no_connect"))
    )
    (net (code "142") (name "unconnected-(CN3-Pad133)") (class "Default")
      (node (ref "CN3") (pin "133") (pinfunction "133_133") (pintype "passive+no_connect"))
    )
    (net (code "143") (name "unconnected-(CN3-Pad134)") (class "Default")
      (node (ref "CN3") (pin "134") (pinfunction "134_134") (pintype "passive+no_connect"))
    )
    (net (code "144") (name "unconnected-(CN3-Pad136)") (class "Default")
      (node (ref "CN3") (pin "136") (pinfunction "136_136") (pintype "passive+no_connect"))
    )
    (net (code "145") (name "unconnected-(CN3-Pad137)") (class "Default")
      (node (ref "CN3") (pin "137") (pinfunction "137_137") (pintype "passive+no_connect"))
    )
    (net (code "146") (name "unconnected-(CN3-Pad139)") (class "Default")
      (node (ref "CN3") (pin "139") (pinfunction "139_139") (pintype "passive+no_connect"))
    )
    (net (code "147") (name "unconnected-(CN3-Pad140)") (class "Default")
      (node (ref "CN3") (pin "140") (pinfunction "140_140") (pintype "passive+no_connect"))
    )
    (net (code "148") (name "unconnected-(CN3-Pad142)") (class "Default")
      (node (ref "CN3") (pin "142") (pinfunction "142_142") (pintype "passive+no_connect"))
    )
    (net (code "149") (name "unconnected-(CN3-Pad143)") (class "Default")
      (node (ref "CN3") (pin "143") (pinfunction "143_143") (pintype "passive+no_connect"))
    )
    (net (code "150") (name "unconnected-(CN3-Pad145)") (class "Default")
      (node (ref "CN3") (pin "145") (pinfunction "145_145") (pintype "passive+no_connect"))
    )
    (net (code "151") (name "unconnected-(CN3-Pad148)") (class "Default")
      (node (ref "CN3") (pin "148") (pinfunction "148_148") (pintype "passive+no_connect"))
    )
    (net (code "152") (name "unconnected-(CN3-Pad149)") (class "Default")
      (node (ref "CN3") (pin "149") (pinfunction "149_149") (pintype "passive+no_connect"))
    )
    (net (code "153") (name "unconnected-(CN3-Pad150)") (class "Default")
      (node (ref "CN3") (pin "150") (pinfunction "150_150") (pintype "passive+no_connect"))
    )
    (net (code "154") (name "unconnected-(CN3-Pad151)") (class "Default")
      (node (ref "CN3") (pin "151") (pinfunction "151_151") (pintype "passive+no_connect"))
    )
    (net (code "155") (name "unconnected-(CN3-Pad154)") (class "Default")
      (node (ref "CN3") (pin "154") (pinfunction "154_154") (pintype "passive+no_connect"))
    )
    (net (code "156") (name "unconnected-(CN3-Pad155)") (class "Default")
      (node (ref "CN3") (pin "155") (pinfunction "155_155") (pintype "passive+no_connect"))
    )
    (net (code "157") (name "unconnected-(CN3-Pad156)") (class "Default")
      (node (ref "CN3") (pin "156") (pinfunction "156_156") (pintype "passive+no_connect"))
    )
    (net (code "158") (name "unconnected-(CN3-Pad157)") (class "Default")
      (node (ref "CN3") (pin "157") (pinfunction "157_157") (pintype "passive+no_connect"))
    )
    (net (code "159") (name "unconnected-(CN3-Pad160)") (class "Default")
      (node (ref "CN3") (pin "160") (pinfunction "160_160") (pintype "passive+no_connect"))
    )
    (net (code "160") (name "unconnected-(CN3-Pad161)") (class "Default")
      (node (ref "CN3") (pin "161") (pinfunction "161_161") (pintype "passive+no_connect"))
    )
    (net (code "161") (name "unconnected-(CN3-Pad162)") (class "Default")
      (node (ref "CN3") (pin "162") (pinfunction "162_162") (pintype "passive+no_connect"))
    )
    (net (code "162") (name "unconnected-(CN3-Pad163)") (class "Default")
      (node (ref "CN3") (pin "163") (pinfunction "163_163") (pintype "passive+no_connect"))
    )
    (net (code "163") (name "unconnected-(CN3-Pad166)") (class "Default")
      (node (ref "CN3") (pin "166") (pinfunction "166_166") (pintype "passive+no_connect"))
    )
    (net (code "164") (name "unconnected-(CN3-Pad167)") (class "Default")
      (node (ref "CN3") (pin "167") (pinfunction "167_167") (pintype "passive+no_connect"))
    )
    (net (code "165") (name "unconnected-(CN3-Pad168)") (class "Default")
      (node (ref "CN3") (pin "168") (pinfunction "168_168") (pintype "passive+no_connect"))
    )
    (net (code "166") (name "unconnected-(CN3-Pad169)") (class "Default")
      (node (ref "CN3") (pin "169") (pinfunction "169_169") (pintype "passive+no_connect"))
    )
    (net (code "167") (name "unconnected-(CN3-Pad172)") (class "Default")
      (node (ref "CN3") (pin "172") (pinfunction "172_172") (pintype "passive+no_connect"))
    )
    (net (code "168") (name "unconnected-(CN3-Pad173)") (class "Default")
      (node (ref "CN3") (pin "173") (pinfunction "173_173") (pintype "passive+no_connect"))
    )
    (net (code "169") (name "unconnected-(CN3-Pad174)") (class "Default")
      (node (ref "CN3") (pin "174") (pinfunction "174_174") (pintype "passive+no_connect"))
    )
    (net (code "170") (name "unconnected-(CN3-Pad175)") (class "Default")
      (node (ref "CN3") (pin "175") (pinfunction "175_175") (pintype "passive+no_connect"))
    )
    (net (code "171") (name "unconnected-(CN3-Pad178)") (class "Default")
      (node (ref "CN3") (pin "178") (pinfunction "178_178") (pintype "passive+no_connect"))
    )
    (net (code "172") (name "unconnected-(CN3-Pad179)") (class "Default")
      (node (ref "CN3") (pin "179") (pinfunction "179_179") (pintype "passive+no_connect"))
    )
    (net (code "173") (name "unconnected-(CN3-Pad180)") (class "Default")
      (node (ref "CN3") (pin "180") (pinfunction "180_180") (pintype "passive+no_connect"))
    )
    (net (code "174") (name "unconnected-(CN3-Pad181)") (class "Default")
      (node (ref "CN3") (pin "181") (pinfunction "181_181") (pintype "passive+no_connect"))
    )
    (net (code "175") (name "unconnected-(CN3-Pad182)") (class "Default")
      (node (ref "CN3") (pin "182") (pinfunction "182_182") (pintype "passive+no_connect"))
    )
    (net (code "176") (name "unconnected-(CN3-Pad183)") (class "Default")
      (node (ref "CN3") (pin "183") (pinfunction "183_183") (pintype "passive+no_connect"))
    )
    (net (code "177") (name "unconnected-(CN3-Pad184)") (class "Default")
      (node (ref "CN3") (pin "184") (pinfunction "184_184") (pintype "passive+no_connect"))
    )
    (net (code "178") (name "unconnected-(CN3-Pad186)") (class "Default")
      (node (ref "CN3") (pin "186") (pinfunction "186_186") (pintype "passive+no_connect"))
    )
    (net (code "179") (name "unconnected-(CN3-Pad188)") (class "Default")
      (node (ref "CN3") (pin "188") (pinfunction "188_188") (pintype "passive+no_connect"))
    )
    (net (code "180") (name "unconnected-(CN3-Pad190)") (class "Default")
      (node (ref "CN3") (pin "190") (pinfunction "190_190") (pintype "passive+no_connect"))
    )
    (net (code "181") (name "unconnected-(CN3-Pad192)") (class "Default")
      (node (ref "CN3") (pin "192") (pinfunction "192_192") (pintype "passive+no_connect"))
    )
    (net (code "182") (name "unconnected-(CN3-Pad193)") (class "Default")
      (node (ref "CN3") (pin "193") (pinfunction "193_193") (pintype "passive+no_connect"))
    )
    (net (code "183") (name "unconnected-(CN3-Pad194)") (class "Default")
      (node (ref "CN3") (pin "194") (pinfunction "194_194") (pintype "passive+no_connect"))
    )
    (net (code "184") (name "unconnected-(CN3-Pad195)") (class "Default")
      (node (ref "CN3") (pin "195") (pinfunction "195_195") (pintype "passive+no_connect"))
    )
    (net (code "185") (name "unconnected-(CN3-Pad196)") (class "Default")
      (node (ref "CN3") (pin "196") (pinfunction "196_196") (pintype "passive+no_connect"))
    )
    (net (code "186") (name "unconnected-(CN3-Pad197)") (class "Default")
      (node (ref "CN3") (pin "197") (pinfunction "197_197") (pintype "passive+no_connect"))
    )
    (net (code "187") (name "unconnected-(CN3-Pad198)") (class "Default")
      (node (ref "CN3") (pin "198") (pinfunction "198_198") (pintype "passive+no_connect"))
    )
    (net (code "188") (name "unconnected-(CN3-Pad199)") (class "Default")
      (node (ref "CN3") (pin "199") (pinfunction "199_199") (pintype "passive+no_connect"))
    )
    (net (code "189") (name "unconnected-(CN3-Pad202)") (class "Default")
      (node (ref "CN3") (pin "202") (pinfunction "202_202") (pintype "passive+no_connect"))
    )
    (net (code "190") (name "unconnected-(CN3-Pad203)") (class "Default")
      (node (ref "CN3") (pin "203") (pinfunction "203_203") (pintype "passive+no_connect"))
    )
    (net (code "191") (name "unconnected-(CN3-Pad204)") (class "Default")
      (node (ref "CN3") (pin "204") (pinfunction "204_204") (pintype "passive+no_connect"))
    )
    (net (code "192") (name "unconnected-(CN3-Pad205)") (class "Default")
      (node (ref "CN3") (pin "205") (pinfunction "205_205") (pintype "passive+no_connect"))
    )
    (net (code "193") (name "unconnected-(CN3-Pad206)") (class "Default")
      (node (ref "CN3") (pin "206") (pinfunction "206_206") (pintype "passive+no_connect"))
    )
    (net (code "194") (name "unconnected-(CN3-Pad207)") (class "Default")
      (node (ref "CN3") (pin "207") (pinfunction "207_207") (pintype "passive+no_connect"))
    )
    (net (code "195") (name "unconnected-(CN3-Pad208)") (class "Default")
      (node (ref "CN3") (pin "208") (pinfunction "208_208") (pintype "passive+no_connect"))
    )
    (net (code "196") (name "unconnected-(CN3-Pad209)") (class "Default")
      (node (ref "CN3") (pin "209") (pinfunction "209_209") (pintype "passive+no_connect"))
    )
    (net (code "197") (name "unconnected-(CN3-Pad211)") (class "Default")
      (node (ref "CN3") (pin "211") (pinfunction "211_211") (pintype "passive+no_connect"))
    )
    (net (code "198") (name "unconnected-(CN3-Pad212)") (class "Default")
      (node (ref "CN3") (pin "212") (pinfunction "212_212") (pintype "passive+no_connect"))
    )
    (net (code "199") (name "unconnected-(CN3-Pad213)") (class "Default")
      (node (ref "CN3") (pin "213") (pinfunction "213_213") (pintype "passive+no_connect"))
    )
    (net (code "200") (name "unconnected-(CN3-Pad215)") (class "Default")
      (node (ref "CN3") (pin "215") (pinfunction "215_215") (pintype "passive+no_connect"))
    )
    (net (code "201") (name "unconnected-(CN3-Pad216)") (class "Default")
      (node (ref "CN3") (pin "216") (pinfunction "216_216") (pintype "passive+no_connect"))
    )
    (net (code "202") (name "unconnected-(CN3-Pad218)") (class "Default")
      (node (ref "CN3") (pin "218") (pinfunction "218_218") (pintype "passive+no_connect"))
    )
    (net (code "203") (name "unconnected-(CN3-Pad220)") (class "Default")
      (node (ref "CN3") (pin "220") (pinfunction "220_220") (pintype "passive+no_connect"))
    )
    (net (code "204") (name "unconnected-(CN3-Pad222)") (class "Default")
      (node (ref "CN3") (pin "222") (pinfunction "222_222") (pintype "passive+no_connect"))
    )
    (net (code "205") (name "unconnected-(CN3-Pad224)") (class "Default")
      (node (ref "CN3") (pin "224") (pinfunction "224_224") (pintype "passive+no_connect"))
    )
    (net (code "206") (name "unconnected-(CN3-Pad226)") (class "Default")
      (node (ref "CN3") (pin "226") (pinfunction "226_226") (pintype "passive+no_connect"))
    )
    (net (code "207") (name "unconnected-(CN3-Pad228)") (class "Default")
      (node (ref "CN3") (pin "228") (pinfunction "228_228") (pintype "passive+no_connect"))
    )
    (net (code "208") (name "unconnected-(CN3-Pad230)") (class "Default")
      (node (ref "CN3") (pin "230") (pinfunction "230_230") (pintype "passive+no_connect"))
    )
    (net (code "209") (name "unconnected-(CN3-Pad232)") (class "Default")
      (node (ref "CN3") (pin "232") (pinfunction "232_232") (pintype "passive+no_connect"))
    )
    (net (code "210") (name "unconnected-(CN3-Pad233)") (class "Default")
      (node (ref "CN3") (pin "233") (pinfunction "233_233") (pintype "passive+no_connect"))
    )
    (net (code "211") (name "unconnected-(CN3-Pad234)") (class "Default")
      (node (ref "CN3") (pin "234") (pinfunction "234_234") (pintype "passive+no_connect"))
    )
    (net (code "212") (name "unconnected-(CN3-Pad235)") (class "Default")
      (node (ref "CN3") (pin "235") (pinfunction "235_235") (pintype "passive+no_connect"))
    )
    (net (code "213") (name "unconnected-(CN3-Pad236)") (class "Default")
      (node (ref "CN3") (pin "236") (pinfunction "236_236") (pintype "passive+no_connect"))
    )
    (net (code "214") (name "unconnected-(CN3-Pad237)") (class "Default")
      (node (ref "CN3") (pin "237") (pinfunction "237_237") (pintype "passive+no_connect"))
    )
    (net (code "215") (name "unconnected-(CN3-Pad238)") (class "Default")
      (node (ref "CN3") (pin "238") (pinfunction "238_238") (pintype "passive+no_connect"))
    )
    (net (code "216") (name "unconnected-(U5-A1-Pad1)") (class "Default")
      (node (ref "U5") (pin "1") (pinfunction "A1_1") (pintype "passive+no_connect"))
    )
    (net (code "217") (name "unconnected-(U5-A2-Pad3)") (class "Default")
      (node (ref "U5") (pin "3") (pinfunction "A2_3") (pintype "passive+no_connect"))
    )
    (net (code "218") (name "unconnected-(U5-A3-Pad4)") (class "Default")
      (node (ref "U5") (pin "4") (pinfunction "A3_4") (pintype "passive+no_connect"))
    )
    (net (code "219") (name "unconnected-(U5-A4-Pad5)") (class "Default")
      (node (ref "U5") (pin "5") (pinfunction "A4_5") (pintype "passive+no_connect"))
    )
    (net (code "220") (name "unconnected-(U5-B1-Pad20)") (class "Default")
      (node (ref "U5") (pin "20") (pinfunction "B1_20") (pintype "passive+no_connect"))
    )
    (net (code "221") (name "unconnected-(U5-B2-Pad18)") (class "Default")
      (node (ref "U5") (pin "18") (pinfunction "B2_18") (pintype "passive+no_connect"))
    )
    (net (code "222") (name "unconnected-(U5-B3-Pad17)") (class "Default")
      (node (ref "U5") (pin "17") (pinfunction "B3_17") (pintype "passive+no_connect"))
    )
    (net (code "223") (name "unconnected-(U5-B4-Pad16)") (class "Default")
      (node (ref "U5") (pin "16") (pinfunction "B4_16") (pintype "passive+no_connect"))
    )
  )
)
